# XDM-3_3_SCH.net
KiCad netlist of a schematic drawn in Altium Designer
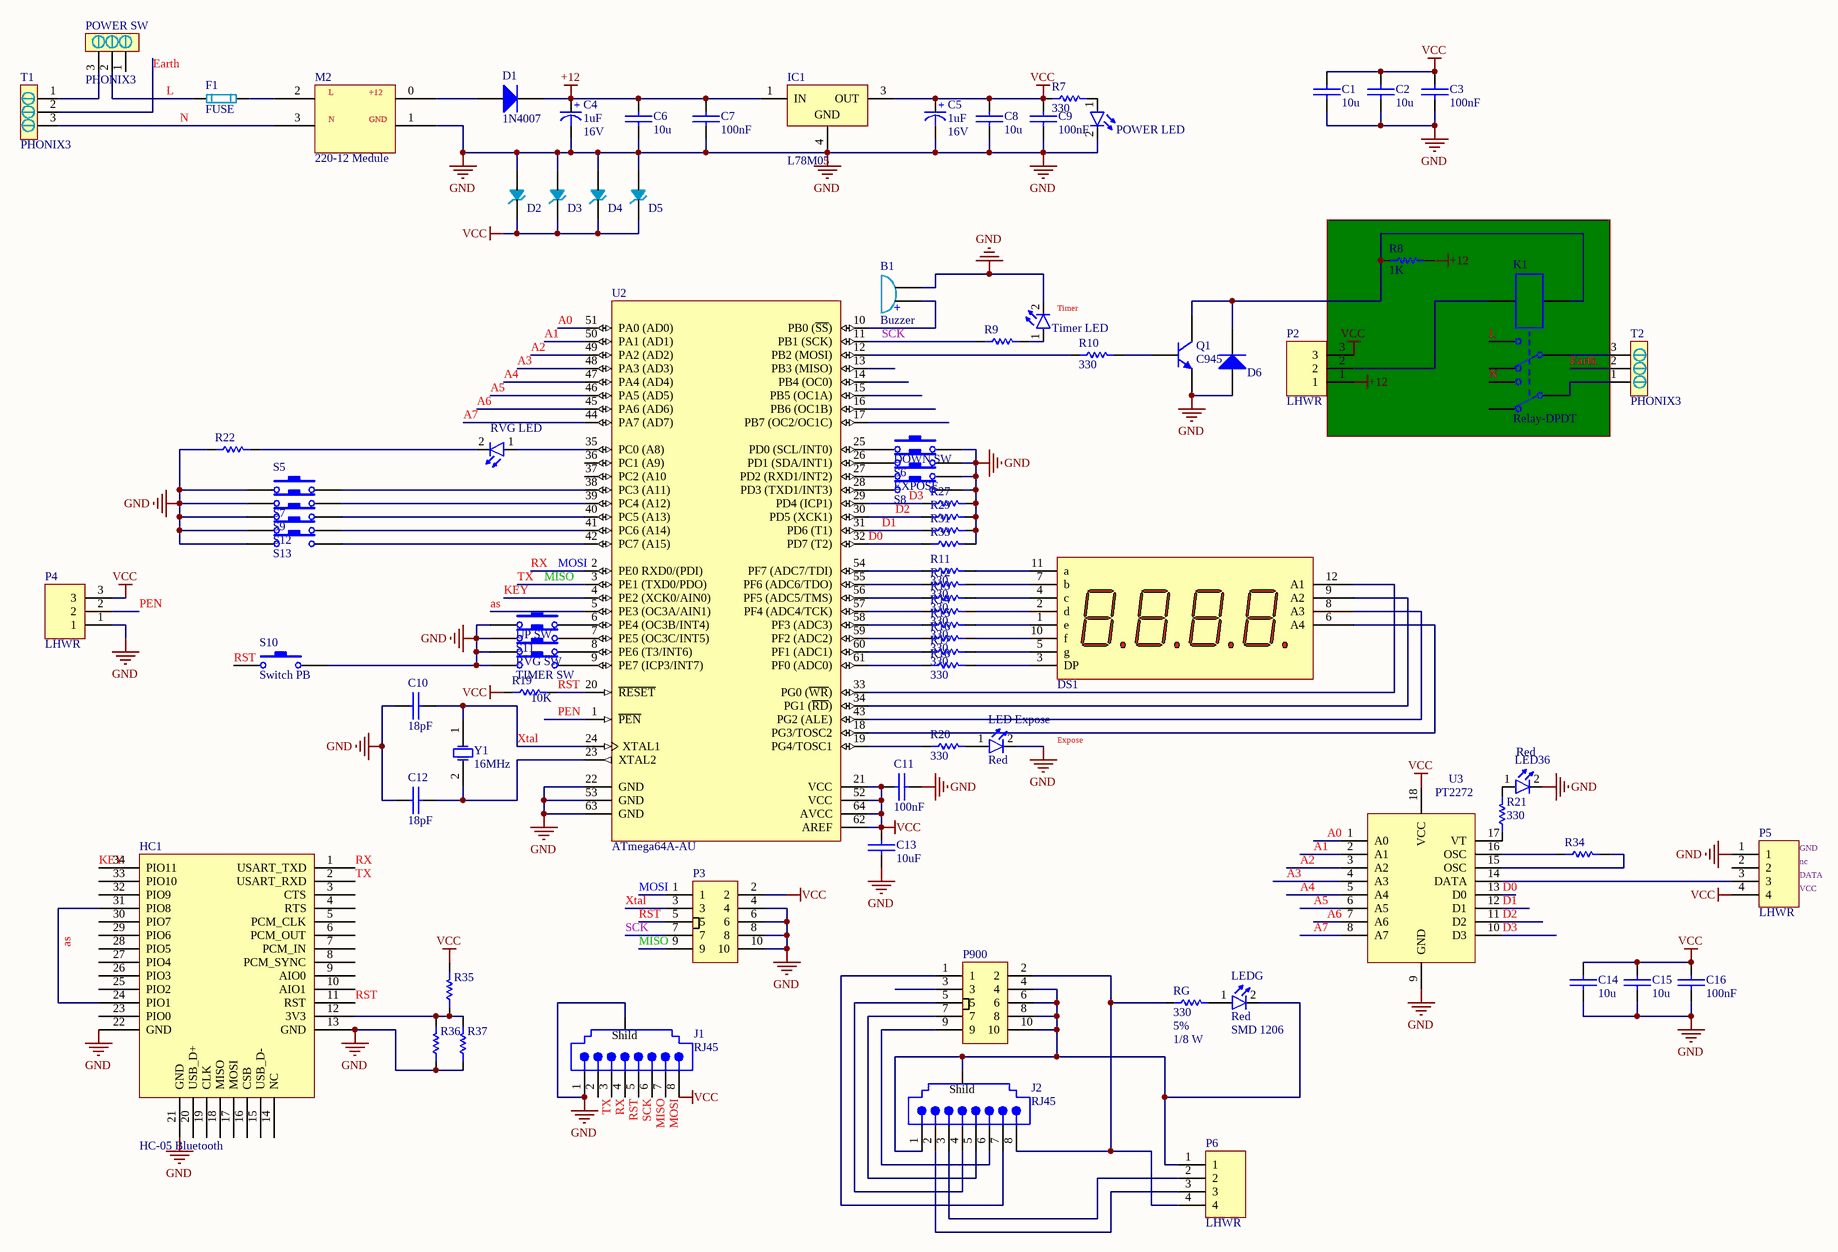
[diagram p0: XDM-3.3_SCH.SchDoc]

(export (version "E")
  (design (tool "Eeschema 10.0.6"))
  (components
    (comp (ref "B1")
      (value "Buzzer")
      (footprint "Buzzer")
      (fields (field (name "DESIGNER") "Hamed Jafarzadeh"))
      (libsource (lib "R2T Team Library") (part "Buzzer"))
    )
    (comp (ref "C1")
      (value "10u")
      (footprint "SMD_CAP_1206")
      (description "Bipolar Capacitor")
      (fields (field (name "VOLTAGE") "100V") (field (name "DESIGNER") "Saeid Jorablo"))
      (libsource (lib "My Library") (part "Cap-Bipolar"))
    )
    (comp (ref "C2")
      (value "10u")
      (footprint "SMD_CAP_1206")
      (description "Bipolar Capacitor")
      (fields (field (name "VOLTAGE") "100V") (field (name "DESIGNER") "Saeid Jorablo"))
      (libsource (lib "My Library") (part "Cap-Bipolar"))
    )
    (comp (ref "C3")
      (value "100nF")
      (footprint "SMD_CAP_1206")
      (description "Bipolar Capacitor")
      (fields (field (name "VOLTAGE") "100V") (field (name "DESIGNER") "Saeid Jorablo"))
      (libsource (lib "My Library") (part "Cap-Bipolar"))
    )
    (comp (ref "C4")
      (value "1uF")
      (footprint "cap 04")
      (description "Polar Capacitor")
      (fields (field (name "VOLTAGE") "16V") (field (name "DESIGNER") "Saeid Jorablo"))
      (libsource (lib "My Library") (part "Cap-Polar"))
    )
    (comp (ref "C5")
      (value "1uF")
      (footprint "cap 04")
      (description "Polar Capacitor")
      (fields (field (name "VOLTAGE") "16V") (field (name "DESIGNER") "Saeid Jorablo"))
      (libsource (lib "My Library") (part "Cap-Polar"))
    )
    (comp (ref "C6")
      (value "10u")
      (footprint "SMD_CAP_1206")
      (description "Bipolar Capacitor")
      (fields (field (name "VOLTAGE") "100V") (field (name "DESIGNER") "Saeid Jorablo"))
      (libsource (lib "My Library") (part "Cap-Bipolar"))
    )
    (comp (ref "C7")
      (value "100nF")
      (footprint "SMD_CAP_1206")
      (description "Bipolar Capacitor")
      (fields (field (name "VOLTAGE") "100V") (field (name "DESIGNER") "Saeid Jorablo"))
      (libsource (lib "My Library") (part "Cap-Bipolar"))
    )
    (comp (ref "C8")
      (value "10u")
      (footprint "SMD_CAP_1206")
      (description "Bipolar Capacitor")
      (fields (field (name "VOLTAGE") "100V") (field (name "DESIGNER") "Saeid Jorablo"))
      (libsource (lib "My Library") (part "Cap-Bipolar"))
    )
    (comp (ref "C9")
      (value "100nF")
      (footprint "SMD_CAP_1206")
      (description "Bipolar Capacitor")
      (fields (field (name "VOLTAGE") "100V") (field (name "DESIGNER") "Saeid Jorablo"))
      (libsource (lib "My Library") (part "Cap-Bipolar"))
    )
    (comp (ref "C10")
      (value "18pF")
      (footprint "SMD_CAP_0805")
      (description "Bipolar Capacitor")
      (fields (field (name "VOLTAGE") "100V") (field (name "DESIGNER") "Saeid Jorablo"))
      (libsource (lib "My Library") (part "Cap-Bipolar"))
    )
    (comp (ref "C11")
      (value "100nF")
      (footprint "SMD_CAP_0805")
      (description "Bipolar Capacitor")
      (fields (field (name "VOLTAGE") "100V") (field (name "DESIGNER") "Saeid Jorablo"))
      (libsource (lib "My Library") (part "Cap-Bipolar"))
    )
    (comp (ref "C12")
      (value "18pF")
      (footprint "SMD_CAP_0805")
      (description "Bipolar Capacitor")
      (fields (field (name "VOLTAGE") "100V") (field (name "DESIGNER") "Saeid Jorablo"))
      (libsource (lib "My Library") (part "Cap-Bipolar"))
    )
    (comp (ref "C13")
      (value "10uF")
      (footprint "SMD_CAP_1206")
      (description "Bipolar Capacitor")
      (fields (field (name "VOLTAGE") "100V") (field (name "DESIGNER") "Saeid Jorablo"))
      (libsource (lib "My Library") (part "Cap-Bipolar"))
    )
    (comp (ref "C14")
      (value "10u")
      (footprint "SMD_CAP_1206")
      (description "Bipolar Capacitor")
      (fields (field (name "VOLTAGE") "100V") (field (name "DESIGNER") "Saeid Jorablo"))
      (libsource (lib "My Library") (part "Cap-Bipolar"))
    )
    (comp (ref "C15")
      (value "10u")
      (footprint "SMD_CAP_1206")
      (description "Bipolar Capacitor")
      (fields (field (name "VOLTAGE") "100V") (field (name "DESIGNER") "Saeid Jorablo"))
      (libsource (lib "My Library") (part "Cap-Bipolar"))
    )
    (comp (ref "C16")
      (value "100nF")
      (footprint "SMD_CAP_1206")
      (description "Bipolar Capacitor")
      (fields (field (name "VOLTAGE") "100V") (field (name "DESIGNER") "Saeid Jorablo"))
      (libsource (lib "My Library") (part "Cap-Bipolar"))
    )
    (comp (ref "D1")
      (value "1N4007")
      (footprint "My_DO-41")
      (description "1 Amp Diode")
      (libsource (lib "MyAltiumLib1") (part "1N4007"))
    )
    (comp (ref "D2")
      (value "Diode Zener SMD")
      (footprint "DIOMELF3615N")
      (fields (field (name "DESIGNER") "Hamed Jafarzadeh"))
      (libsource (lib "R2T Team Library") (part "Diode Zener SMD"))
    )
    (comp (ref "D3")
      (value "Diode Zener SMD")
      (footprint "DIOMELF3615N")
      (fields (field (name "DESIGNER") "Hamed Jafarzadeh"))
      (libsource (lib "R2T Team Library") (part "Diode Zener SMD"))
    )
    (comp (ref "D4")
      (value "Diode Zener SMD")
      (footprint "DIOMELF3615N")
      (fields (field (name "DESIGNER") "Hamed Jafarzadeh"))
      (libsource (lib "R2T Team Library") (part "Diode Zener SMD"))
    )
    (comp (ref "D5")
      (value "Diode Zener SMD")
      (footprint "DIOMELF3615N")
      (fields (field (name "DESIGNER") "Hamed Jafarzadeh"))
      (libsource (lib "R2T Team Library") (part "Diode Zener SMD"))
    )
    (comp (ref "D6")
      (value "1N4007")
      (footprint "My_DO-41")
      (description "1 Amp Diode")
      (libsource (lib "MyAltiumLib1") (part "1N4007"))
    )
    (comp (ref "DOWN SW")
      (value "Switch PB")
      (footprint "Switch - Push to On")
      (description "Push Button Switch")
      (libsource (lib "Electrovolt Lib") (part "Switch PB"))
    )
    (comp (ref "DS1")
      (value "7Segment-4Digit-CA")
      (footprint "7segCA")
      (description "7-Segment Display: CA")
      (fields (field (name "PUBLISHER") "www.picpars.com") (field (name "DESIGNER") "Seyed Mohsen Ghasemain"))
      (libsource (lib "usefully_Library") (part "7Seg-4Digit-CA"))
    )
    (comp (ref "EXPOSE")
      (value "Switch PB")
      (footprint "Switch - Push to On")
      (description "Push Button Switch")
      (libsource (lib "Electrovolt Lib") (part "Switch PB"))
    )
    (comp (ref "F1") (value "FUSE") (footprint "FUSE_1") (libsource (lib "Devices") (part "FUSE")))
    (comp (ref "HC1")
      (value "HC-05 Bluetooth")
      (footprint "HC-05")
      (libsource (lib "R2T Team Library") (part "HC-05 Bluetooth"))
    )
    (comp (ref "IC1")
      (value "L78M05")
      (footprint "TO-252")
      (description "Precision 500mA Regulator")
      (libsource (lib "My Library") (part "L78M05"))
    )
    (comp (ref "J1")
      (value "RJ45")
      (footprint "My_RJ45")
      (description "Right Angle, Standard Profile, RJ45-Keyed, Flange Mount PCB Jack")
      (fields (field (name "PUBLISHER") "Altium Limited"))
      (libsource (lib "MyAltiumLib1") (part "RJ45"))
    )
    (comp (ref "J2")
      (value "RJ45")
      (footprint "My_RJ45")
      (description "Right Angle, Standard Profile, RJ45-Keyed, Flange Mount PCB Jack")
      (fields (field (name "PUBLISHER") "Altium Limited"))
      (libsource (lib "MyAltiumLib1") (part "RJ45"))
    )
    (comp (ref "K1")
      (value "Relay-DPDT")
      (footprint "My_REL_cochick")
      (description "Dual-Pole Dual-Throw Relay")
      (fields (field (name "PUBLISHER") "Altium Limited"))
      (libsource (lib "MyAltiumLib1") (part "Relay-DPDT"))
    )
    (comp (ref "LED Expose")
      (value "Red")
      (footprint "LED-3mm")
      (description "LED")
      (fields (field (name "COLOR") "Red") (field (name "DESIGNER") "Saeid Jorablo"))
      (libsource (lib "My Library") (part "LED"))
    )
    (comp (ref "LED36")
      (value "Red")
      (footprint "LED-3mm")
      (description "LED")
      (fields (field (name "COLOR") "Red") (field (name "DESIGNER") "Saeid Jorablo"))
      (libsource (lib "My Library") (part "LED"))
    )
    (comp (ref "LEDG")
      (value "Red")
      (footprint "LED-3mm")
      (description "LED")
      (fields
        (field (name "COLOR") "Red")
        (field (name "SIZE") "SMD 1206")
        (field (name "DESIGNER") "Saeid Jorablo")
      )
      (libsource (lib "My Library") (part "LED"))
    )
    (comp (ref "M2")
      (value "220-12 Medule")
      (footprint "AC-DC 220-12")
      (libsource (lib "Soga Library") (part "220-12 Medule"))
    )
    (comp (ref "P2")
      (value "LHWR")
      (footprint "Polarized Header 3")
      (fields (field (name "DESIGNER:") "Hamed Jafarzadeh - www.R2T.ir"))
      (libsource (lib "R2T Team Library") (part "3pin LHWR"))
    )
    (comp (ref "P3")
      (value "BoxHeader 2x5")
      (footprint "Box Header 2x5")
      (fields (field (name "DESIGNER") "HamedJafarzadeh - ww.R2T.ir"))
      (libsource (lib "R2T Team Library") (part "BoxHeader 2x5"))
    )
    (comp (ref "P4")
      (value "LHWR")
      (footprint "Polarized Header 3")
      (fields (field (name "DESIGNER:") "Hamed Jafarzadeh - www.R2T.ir"))
      (libsource (lib "R2T Team Library") (part "3pin LHWR"))
    )
    (comp (ref "P5")
      (value "LHWR")
      (footprint "Polarized Header 4")
      (fields (field (name "DESIGNER:") "Hamed Jafarzadeh - www.R2T.ir"))
      (libsource (lib "R2T Team Library") (part "4pin LHWR"))
    )
    (comp (ref "P6")
      (value "LHWR")
      (footprint "Polarized Header 4")
      (fields (field (name "DESIGNER:") "Hamed Jafarzadeh - www.R2T.ir"))
      (libsource (lib "R2T Team Library") (part "4pin LHWR"))
    )
    (comp (ref "P900")
      (value "BoxHeader 2x5")
      (footprint "Box Header 2x5")
      (fields (field (name "DESIGNER") "HamedJafarzadeh - ww.R2T.ir"))
      (libsource (lib "R2T Team Library") (part "BoxHeader 2x5"))
    )
    (comp (ref "POWER LED")
      (value "Red")
      (footprint "LED-3mm")
      (description "LED")
      (fields (field (name "DESIGNER") "Saeid Jorablo"))
      (libsource (lib "My Library") (part "LED"))
    )
    (comp (ref "POWER SW")
      (value "PHONIX3")
      (footprint "PHONIX3")
      (libsource (lib "My_lib_new") (part "PHONIX3"))
    )
    (comp (ref "Q1")
      (value "C945")
      (footprint "C945")
      (description "NPN Transistor")
      (fields (field (name "DESIGNER") "Saeid Jorablo"))
      (libsource (lib "Electrovolt Lib") (part "C945"))
    )
    (comp (ref "R7")
      (value "330")
      (footprint "RES 0805 (2012X06L)")
      (description "Resistor")
      (fields (field (name "TOLERANCE") "5%") (field (name "POWER") "1/8 W"))
      (libsource (lib "My Library") (part "Resistor"))
    )
    (comp (ref "R8")
      (value "1K")
      (footprint "RES 0805 (2012X06L)")
      (description "Resistor")
      (fields (field (name "TOLERANCE") "5%") (field (name "POWER") "1/8 W"))
      (libsource (lib "My Library") (part "Resistor"))
    )
    (comp (ref "R9")
      (value "330")
      (footprint "RES 0805 (2012X06L)")
      (description "Resistor")
      (fields (field (name "TOLERANCE") "5%") (field (name "POWER") "1/8 W"))
      (libsource (lib "My Library") (part "Resistor"))
    )
    (comp (ref "R10")
      (value "330")
      (footprint "RES 0805 (2012X06L)")
      (description "Resistor")
      (fields (field (name "TOLERANCE") "5%") (field (name "POWER") "1/8 W"))
      (libsource (lib "Electrovolt Lib") (part "Resistor"))
    )
    (comp (ref "R11")
      (value "330")
      (footprint "RES 0805 (2012X06L)")
      (description "Resistor")
      (fields (field (name "TOLERANCE") "5%") (field (name "POWER") "1/8 W"))
      (libsource (lib "My Library") (part "Resistor"))
    )
    (comp (ref "R12")
      (value "330")
      (footprint "RES 0805 (2012X06L)")
      (description "Resistor")
      (fields (field (name "TOLERANCE") "5%") (field (name "POWER") "1/8 W"))
      (libsource (lib "My Library") (part "Resistor"))
    )
    (comp (ref "R13")
      (value "330")
      (footprint "RES 0805 (2012X06L)")
      (description "Resistor")
      (fields (field (name "TOLERANCE") "5%") (field (name "POWER") "1/8 W"))
      (libsource (lib "My Library") (part "Resistor"))
    )
    (comp (ref "R14")
      (value "330")
      (footprint "RES 0805 (2012X06L)")
      (description "Resistor")
      (fields (field (name "TOLERANCE") "5%") (field (name "POWER") "1/8 W"))
      (libsource (lib "My Library") (part "Resistor"))
    )
    (comp (ref "R15")
      (value "330")
      (footprint "RES 0805 (2012X06L)")
      (description "Resistor")
      (fields (field (name "TOLERANCE") "5%") (field (name "POWER") "1/8 W"))
      (libsource (lib "My Library") (part "Resistor"))
    )
    (comp (ref "R16")
      (value "330")
      (footprint "RES 0805 (2012X06L)")
      (description "Resistor")
      (fields (field (name "TOLERANCE") "5%") (field (name "POWER") "1/8 W"))
      (libsource (lib "My Library") (part "Resistor"))
    )
    (comp (ref "R17")
      (value "330")
      (footprint "RES 0805 (2012X06L)")
      (description "Resistor")
      (fields (field (name "TOLERANCE") "5%") (field (name "POWER") "1/8 W"))
      (libsource (lib "My Library") (part "Resistor"))
    )
    (comp (ref "R18")
      (value "330")
      (footprint "RES 0805 (2012X06L)")
      (description "Resistor")
      (fields (field (name "TOLERANCE") "5%") (field (name "POWER") "1/8 W"))
      (libsource (lib "My Library") (part "Resistor"))
    )
    (comp (ref "R19")
      (value "10K")
      (footprint "RES 0805 (2012X06L)")
      (description "Resistor")
      (fields (field (name "TOLERANCE") "5%") (field (name "POWER") "1/8 W"))
      (libsource (lib "My Library") (part "Resistor"))
    )
    (comp (ref "R20")
      (value "330")
      (footprint "RES 0805 (2012X06L)")
      (description "Resistor")
      (fields (field (name "TOLERANCE") "5%") (field (name "POWER") "1/8 W"))
      (libsource (lib "My Library") (part "Resistor"))
    )
    (comp (ref "R21")
      (value "330")
      (footprint "RES 0805 (2012X06L)")
      (description "Resistor")
      (fields (field (name "TOLERANCE") "5%") (field (name "POWER") "1/8 W"))
      (libsource (lib "My Library") (part "Resistor"))
    )
    (comp (ref "R22")
      (value "330")
      (footprint "RES 0805 (2012X06L)")
      (description "Resistor")
      (fields (field (name "TOLERANCE") "5%") (field (name "POWER") "1/8 W"))
      (libsource (lib "My Library") (part "Resistor"))
    )
    (comp (ref "R27")
      (value "1K")
      (footprint "RES 0805 (2012X06L)")
      (description "Resistor")
      (fields (field (name "TOLERANCE") "5%") (field (name "POWER") "1/8 W"))
      (libsource (lib "My Library") (part "Resistor"))
    )
    (comp (ref "R29")
      (value "1K")
      (footprint "RES 0805 (2012X06L)")
      (description "Resistor")
      (fields (field (name "TOLERANCE") "5%") (field (name "POWER") "1/8 W"))
      (libsource (lib "My Library") (part "Resistor"))
    )
    (comp (ref "R31")
      (value "1K")
      (footprint "RES 0805 (2012X06L)")
      (description "Resistor")
      (fields (field (name "TOLERANCE") "5%") (field (name "POWER") "1/8 W"))
      (libsource (lib "My Library") (part "Resistor"))
    )
    (comp (ref "R33")
      (value "1K")
      (footprint "RES 0805 (2012X06L)")
      (description "Resistor")
      (fields (field (name "TOLERANCE") "5%") (field (name "POWER") "1/8 W"))
      (libsource (lib "My Library") (part "Resistor"))
    )
    (comp (ref "R34")
      (value "820k")
      (footprint "RES 0805 (2012X06L)")
      (description "Resistor")
      (fields (field (name "TOLERANCE") "5%") (field (name "POWER") "1/8 W"))
      (libsource (lib "My Library") (part "Resistor"))
    )
    (comp (ref "R35")
      (value "51k")
      (footprint "RES 0805 (2012X06L)")
      (description "Resistor")
      (fields (field (name "TOLERANCE") "5%") (field (name "POWER") "1/8 W"))
      (libsource (lib "My Library") (part "Resistor"))
    )
    (comp (ref "R36")
      (value "100k")
      (footprint "RES 0805 (2012X06L)")
      (description "Resistor")
      (fields (field (name "TOLERANCE") "5%") (field (name "POWER") "1/8 W"))
      (libsource (lib "My Library") (part "Resistor"))
    )
    (comp (ref "R37")
      (value "100k")
      (footprint "RES 0805 (2012X06L)")
      (description "Resistor")
      (fields (field (name "TOLERANCE") "5%") (field (name "POWER") "1/8 W"))
      (libsource (lib "My Library") (part "Resistor"))
    )
    (comp (ref "RG")
      (value "330")
      (footprint "RES 0805 (2012X06L)")
      (description "Resistor")
      (fields (field (name "TOLERANCE") "5%") (field (name "POWER") "1/8 W"))
      (libsource (lib "My Library") (part "Resistor"))
    )
    (comp (ref "RVG LED")
      (value "Red")
      (footprint "LED-3mm")
      (description "LED")
      (fields (field (name "DESIGNER") "Saeid Jorablo"))
      (libsource (lib "My Library") (part "LED"))
    )
    (comp (ref "RVG SW")
      (value "Switch PB")
      (footprint "Switch - Push to On")
      (description "Push Button Switch")
      (libsource (lib "Electrovolt Lib") (part "Switch PB"))
    )
    (comp (ref "S5")
      (value "Switch PB")
      (footprint "Switch - Push to On")
      (description "Push Button Switch")
      (libsource (lib "Electrovolt Lib") (part "Switch PB"))
    )
    (comp (ref "S6")
      (value "Switch PB")
      (footprint "Switch - Push to On")
      (description "Push Button Switch")
      (libsource (lib "Electrovolt Lib") (part "Switch PB"))
    )
    (comp (ref "S7")
      (value "Switch PB")
      (footprint "Switch - Push to On")
      (description "Push Button Switch")
      (libsource (lib "Electrovolt Lib") (part "Switch PB"))
    )
    (comp (ref "S8")
      (value "Switch PB")
      (footprint "Switch - Push to On")
      (description "Push Button Switch")
      (libsource (lib "Electrovolt Lib") (part "Switch PB"))
    )
    (comp (ref "S9")
      (value "Switch PB")
      (footprint "Switch - Push to On")
      (description "Push Button Switch")
      (libsource (lib "Electrovolt Lib") (part "Switch PB"))
    )
    (comp (ref "S10")
      (value "Switch PB")
      (footprint "Switch - Push to On")
      (description "Push Button Switch")
      (libsource (lib "Electrovolt Lib") (part "Switch PB"))
    )
    (comp (ref "S11")
      (value "Switch PB")
      (footprint "Switch - Push to On")
      (description "Push Button Switch")
      (libsource (lib "Electrovolt Lib") (part "Switch PB"))
    )
    (comp (ref "S12")
      (value "Switch PB")
      (footprint "Switch - Push to On")
      (description "Push Button Switch")
      (libsource (lib "Electrovolt Lib") (part "Switch PB"))
    )
    (comp (ref "S13")
      (value "Switch PB")
      (footprint "Switch - Push to On")
      (description "Push Button Switch")
      (libsource (lib "Electrovolt Lib") (part "Switch PB"))
    )
    (comp (ref "T1") (value "PHONIX3") (footprint "PHONIX3") (libsource (lib "") (part "PHONIX3_2")))
    (comp (ref "T2") (value "PHONIX3") (footprint "PHONIX3") (libsource (lib "") (part "PHONIX3_1")))
    (comp (ref "Timer LED")
      (value "Red")
      (footprint "LED-3mm")
      (description "LED")
      (fields (field (name "DESIGNER") "Saeid Jorablo"))
      (libsource (lib "My Library") (part "LED"))
    )
    (comp (ref "TIMER SW")
      (value "Switch PB")
      (footprint "Switch - Push to On")
      (description "Push Button Switch")
      (libsource (lib "Electrovolt Lib") (part "Switch PB"))
    )
    (comp (ref "U2")
      (value "ATmega64A-AU")
      (footprint "64A_M")
      (fields (field (name "PUBLISHER") "Altium Limited"))
      (libsource (lib "Atmel Microcontroller 8-Bit megaAVR") (part "ATmega64A-AU"))
    )
    (comp (ref "U3") (value "PT2272") (footprint "DIP18") (libsource (lib "My_lib_new") (part "PT2272")))
    (comp (ref "UP SW")
      (value "Switch PB")
      (footprint "Switch - Push to On")
      (description "Push Button Switch")
      (libsource (lib "Electrovolt Lib") (part "Switch PB"))
    )
    (comp (ref "Y1")
      (value "16MHz")
      (footprint "XTAL Small")
      (description "XTAL Crystal")
      (libsource (lib "My Library") (part "XTAL"))
    )
  )
  (nets
    (net (code "1") (name "+12") (class "Default")
      (node (ref "C4") (pin "1") (pinfunction "+_1") (pintype "passive"))
      (node (ref "C6") (pin "1") (pinfunction "+_1") (pintype "passive"))
      (node (ref "C7") (pin "1") (pinfunction "+_1") (pintype "passive"))
      (node (ref "D1") (pin "K") (pinfunction "K_K") (pintype "passive"))
      (node (ref "IC1") (pin "1") (pinfunction "IN_1") (pintype "power_in"))
      (node (ref "P2") (pin "1") (pinfunction "1_1") (pintype "passive"))
      (node (ref "R8") (pin "2") (pinfunction "2_2") (pintype "passive"))
    )
    (net (code "2") (name "/A0") (class "Default")
      (node (ref "U2") (pin "51") (pinfunction "PA0_(AD0)_51") (pintype "bidirectional"))
      (node (ref "U3") (pin "1") (pinfunction "A0_1") (pintype "passive"))
    )
    (net (code "3") (name "/A1") (class "Default")
      (node (ref "U2") (pin "50") (pinfunction "PA1_(AD1)_50") (pintype "bidirectional"))
      (node (ref "U3") (pin "2") (pinfunction "A1_2") (pintype "passive"))
    )
    (net (code "4") (name "/A2") (class "Default")
      (node (ref "U2") (pin "49") (pinfunction "PA2_(AD2)_49") (pintype "bidirectional"))
      (node (ref "U3") (pin "3") (pinfunction "A2_3") (pintype "passive"))
    )
    (net (code "5") (name "/A3") (class "Default")
      (node (ref "U2") (pin "48") (pinfunction "PA3_(AD3)_48") (pintype "bidirectional"))
      (node (ref "U3") (pin "4") (pinfunction "A3_4") (pintype "passive"))
    )
    (net (code "6") (name "/A4") (class "Default")
      (node (ref "U2") (pin "47") (pinfunction "PA4_(AD4)_47") (pintype "bidirectional"))
      (node (ref "U3") (pin "5") (pinfunction "A4_5") (pintype "passive"))
    )
    (net (code "7") (name "/A5") (class "Default")
      (node (ref "U2") (pin "46") (pinfunction "PA5_(AD5)_46") (pintype "bidirectional"))
      (node (ref "U3") (pin "6") (pinfunction "A5_6") (pintype "passive"))
    )
    (net (code "8") (name "/A6") (class "Default")
      (node (ref "U2") (pin "45") (pinfunction "PA6_(AD6)_45") (pintype "bidirectional"))
      (node (ref "U3") (pin "7") (pinfunction "A6_7") (pintype "passive"))
    )
    (net (code "9") (name "/A7") (class "Default")
      (node (ref "U2") (pin "44") (pinfunction "PA7_(AD7)_44") (pintype "bidirectional"))
      (node (ref "U3") (pin "8") (pinfunction "A7_8") (pintype "passive"))
    )
    (net (code "10") (name "/D0") (class "Default")
      (node (ref "R33") (pin "1") (pinfunction "1_1") (pintype "passive"))
      (node (ref "U2") (pin "32") (pinfunction "PD7_(T2)_32") (pintype "bidirectional"))
      (node (ref "U3") (pin "13") (pinfunction "D0_13") (pintype "passive"))
    )
    (net (code "11") (name "/D1") (class "Default")
      (node (ref "R31") (pin "1") (pinfunction "1_1") (pintype "passive"))
      (node (ref "U2") (pin "31") (pinfunction "PD6_(T1)_31") (pintype "bidirectional"))
      (node (ref "U3") (pin "12") (pinfunction "D1_12") (pintype "passive"))
    )
    (net (code "12") (name "/D2") (class "Default")
      (node (ref "R29") (pin "1") (pinfunction "1_1") (pintype "passive"))
      (node (ref "U2") (pin "30") (pinfunction "PD5_(XCK1)_30") (pintype "bidirectional"))
      (node (ref "U3") (pin "11") (pinfunction "D2_11") (pintype "passive"))
    )
    (net (code "13") (name "/D3") (class "Default")
      (node (ref "R27") (pin "1") (pinfunction "1_1") (pintype "passive"))
      (node (ref "U2") (pin "29") (pinfunction "PD4_(ICP1)_29") (pintype "bidirectional"))
      (node (ref "U3") (pin "10") (pinfunction "D3_10") (pintype "passive"))
    )
    (net (code "14") (name "/Earth") (class "Default")
      (node (ref "T1") (pin "2") (pintype "passive"))
      (node (ref "T2") (pin "2") (pintype "passive"))
    )
    (net (code "15") (name "/KEY") (class "Default")
      (node (ref "HC1") (pin "34") (pinfunction "PIO11_34") (pintype "passive"))
      (node (ref "U2") (pin "4") (pinfunction "PE2_(XCK0/AIN0)_4") (pintype "bidirectional"))
    )
    (net (code "16") (name "/L") (class "Default")
      (node (ref "F1") (pin "1") (pintype "passive"))
      (node (ref "K1") (pin "S1") (pinfunction "S1_S1") (pintype "passive"))
      (node (ref "POWER SW") (pin "2") (pintype "passive"))
    )
    (net (code "17") (name "/MISO") (class "Default")
      (node (ref "HC1") (pin "2") (pinfunction "USART_RXD_2") (pintype "passive"))
      (node (ref "J1") (pin "2") (pinfunction "2_2") (pintype "passive"))
      (node (ref "J1") (pin "6") (pinfunction "6_6") (pintype "passive"))
      (node (ref "P3") (pin "9") (pinfunction "9_9") (pintype "passive"))
      (node (ref "U2") (pin "3") (pinfunction "PE1_(TXD0/PDO)_3") (pintype "bidirectional"))
    )
    (net (code "18") (name "/MOSI") (class "Default")
      (node (ref "HC1") (pin "1") (pinfunction "USART_TXD_1") (pintype "passive"))
      (node (ref "J1") (pin "3") (pinfunction "3_3") (pintype "passive"))
      (node (ref "J1") (pin "7") (pinfunction "7_7") (pintype "passive"))
      (node (ref "P3") (pin "1") (pinfunction "1_1") (pintype "passive"))
      (node (ref "U2") (pin "2") (pinfunction "PE0_RXD0/(PDI)_2") (pintype "bidirectional"))
    )
    (net (code "19") (name "/N") (class "Default")
      (node (ref "K1") (pin "S2") (pinfunction "S2_S2") (pintype "passive"))
      (node (ref "M2") (pin "3") (pinfunction "3_3") (pintype "passive"))
      (node (ref "T1") (pin "3") (pintype "passive"))
    )
    (net (code "20") (name "/PEN") (class "Default")
      (node (ref "P4") (pin "2") (pinfunction "2_2") (pintype "passive"))
      (node (ref "U2") (pin "1") (pinfunction "~{PEN}_1") (pintype "input"))
    )
    (net (code "21") (name "/RST") (class "Default")
      (node (ref "HC1") (pin "11") (pinfunction "RST_11") (pintype "passive"))
      (node (ref "J1") (pin "4") (pinfunction "4_4") (pintype "passive"))
      (node (ref "P3") (pin "5") (pinfunction "5_5") (pintype "passive"))
      (node (ref "R19") (pin "2") (pinfunction "2_2") (pintype "passive"))
      (node (ref "S10") (pin "1") (pinfunction "1_1") (pintype "passive"))
      (node (ref "U2") (pin "20") (pinfunction "~{RESET}_20") (pintype "input"))
    )
    (net (code "22") (name "/SCK") (class "Default")
      (node (ref "J1") (pin "5") (pinfunction "5_5") (pintype "passive"))
      (node (ref "P3") (pin "7") (pinfunction "7_7") (pintype "passive"))
      (node (ref "R9") (pin "1") (pinfunction "1_1") (pintype "passive"))
      (node (ref "U2") (pin "11") (pinfunction "PB1_(SCK)_11") (pintype "bidirectional"))
    )
    (net (code "23") (name "/Xtal") (class "Default")
      (node (ref "C10") (pin "2") (pinfunction "-_2") (pintype "passive"))
      (node (ref "P3") (pin "3") (pinfunction "3_3") (pintype "passive"))
      (node (ref "U2") (pin "24") (pinfunction "XTAL1_24") (pintype "input"))
      (node (ref "Y1") (pin "1") (pinfunction "OSC1_1") (pintype "passive"))
    )
    (net (code "24") (name "/as") (class "Default")
      (node (ref "HC1") (pin "24") (pinfunction "PIO1_24") (pintype "passive"))
      (node (ref "HC1") (pin "31") (pinfunction "PIO8_31") (pintype "passive"))
      (node (ref "U2") (pin "5") (pinfunction "PE3_(OC3A/AIN1)_5") (pintype "bidirectional"))
    )
    (net (code "25") (name "GND") (class "Default")
      (node (ref "B1") (pin "2") (pinfunction "GND_2") (pintype "passive"))
      (node (ref "C1") (pin "2") (pinfunction "-_2") (pintype "passive"))
      (node (ref "C10") (pin "1") (pinfunction "+_1") (pintype "passive"))
      (node (ref "C11") (pin "1") (pinfunction "+_1") (pintype "passive"))
      (node (ref "C12") (pin "1") (pinfunction "+_1") (pintype "passive"))
      (node (ref "C13") (pin "2") (pinfunction "-_2") (pintype "passive"))
      (node (ref "C14") (pin "2") (pinfunction "-_2") (pintype "passive"))
      (node (ref "C15") (pin "2") (pinfunction "-_2") (pintype "passive"))
      (node (ref "C16") (pin "2") (pinfunction "-_2") (pintype "passive"))
      (node (ref "C2") (pin "2") (pinfunction "-_2") (pintype "passive"))
      (node (ref "C3") (pin "2") (pinfunction "-_2") (pintype "passive"))
      (node (ref "C4") (pin "2") (pinfunction "-_2") (pintype "passive"))
      (node (ref "C5") (pin "2") (pinfunction "-_2") (pintype "passive"))
      (node (ref "C6") (pin "2") (pinfunction "-_2") (pintype "passive"))
      (node (ref "C7") (pin "2") (pinfunction "-_2") (pintype "passive"))
      (node (ref "C8") (pin "2") (pinfunction "-_2") (pintype "passive"))
      (node (ref "C9") (pin "2") (pinfunction "-_2") (pintype "passive"))
      (node (ref "D2") (pin "2") (pintype "passive"))
      (node (ref "D3") (pin "2") (pintype "passive"))
      (node (ref "D4") (pin "2") (pintype "passive"))
      (node (ref "D5") (pin "2") (pintype "passive"))
      (node (ref "D6") (pin "A") (pinfunction "A_A") (pintype "passive"))
      (node (ref "DOWN SW") (pin "2") (pinfunction "2_2") (pintype "passive"))
      (node (ref "EXPOSE") (pin "2") (pinfunction "2_2") (pintype "passive"))
      (node (ref "HC1") (pin "13") (pinfunction "GND_13") (pintype "passive"))
      (node (ref "HC1") (pin "21") (pinfunction "GND_21") (pintype "passive"))
      (node (ref "HC1") (pin "22") (pinfunction "GND_22") (pintype "passive"))
      (node (ref "IC1") (pin "4") (pinfunction "GND_4") (pintype "power_in"))
      (node (ref "J1") (pin "1") (pinfunction "1_1") (pintype "passive"))
      (node (ref "J1") (pin "shild") (pinfunction "Shild_shild") (pintype "passive"))
      (node (ref "LED Expose") (pin "2") (pinfunction "K_2") (pintype "passive"))
      (node (ref "LED36") (pin "2") (pinfunction "K_2") (pintype "passive"))
      (node (ref "M2") (pin "1") (pinfunction "1_1") (pintype "passive"))
      (node (ref "P3") (pin "10") (pinfunction "10_10") (pintype "passive"))
      (node (ref "P3") (pin "4") (pinfunction "4_4") (pintype "passive"))
      (node (ref "P3") (pin "6") (pinfunction "6_6") (pintype "passive"))
      (node (ref "P3") (pin "8") (pinfunction "8_8") (pintype "passive"))
      (node (ref "P4") (pin "1") (pinfunction "1_1") (pintype "passive"))
      (node (ref "P5") (pin "1") (pinfunction "1_1") (pintype "passive"))
      (node (ref "POWER LED") (pin "2") (pinfunction "K_2") (pintype "passive"))
      (node (ref "Q1") (pin "1") (pinfunction "E_1") (pintype "passive"))
      (node (ref "R22") (pin "1") (pinfunction "1_1") (pintype "passive"))
      (node (ref "R27") (pin "2") (pinfunction "2_2") (pintype "passive"))
      (node (ref "R29") (pin "2") (pinfunction "2_2") (pintype "passive"))
      (node (ref "R31") (pin "2") (pinfunction "2_2") (pintype "passive"))
      (node (ref "R33") (pin "2") (pinfunction "2_2") (pintype "passive"))
      (node (ref "R36") (pin "1") (pinfunction "1_1") (pintype "passive"))
      (node (ref "R37") (pin "1") (pinfunction "1_1") (pintype "passive"))
      (node (ref "RVG SW") (pin "1") (pinfunction "1_1") (pintype "passive"))
      (node (ref "S10") (pin "2") (pinfunction "2_2") (pintype "passive"))
      (node (ref "S11") (pin "1") (pinfunction "1_1") (pintype "passive"))
      (node (ref "S12") (pin "1") (pinfunction "1_1") (pintype "passive"))
      (node (ref "S13") (pin "1") (pinfunction "1_1") (pintype "passive"))
      (node (ref "S5") (pin "1") (pinfunction "1_1") (pintype "passive"))
      (node (ref "S6") (pin "2") (pinfunction "2_2") (pintype "passive"))
      (node (ref "S7") (pin "1") (pinfunction "1_1") (pintype "passive"))
      (node (ref "S8") (pin "2") (pinfunction "2_2") (pintype "passive"))
      (node (ref "S9") (pin "1") (pinfunction "1_1") (pintype "passive"))
      (node (ref "TIMER SW") (pin "1") (pinfunction "1_1") (pintype "passive"))
      (node (ref "Timer LED") (pin "2") (pinfunction "K_2") (pintype "passive"))
      (node (ref "U2") (pin "22") (pinfunction "GND_22") (pintype "power_in"))
      (node (ref "U2") (pin "53") (pinfunction "GND_53") (pintype "power_in"))
      (node (ref "U2") (pin "63") (pinfunction "GND_63") (pintype "power_in"))
      (node (ref "U3") (pin "9") (pinfunction "GND_9") (pintype "passive"))
      (node (ref "UP SW") (pin "1") (pinfunction "1_1") (pintype "passive"))
    )
    (net (code "26") (name "Net-(B1-VCC)") (class "Default")
      (node (ref "B1") (pin "1") (pinfunction "VCC_1") (pintype "passive"))
      (node (ref "U2") (pin "10") (pinfunction "PB0_(~{SS})_10") (pintype "bidirectional"))
    )
    (net (code "27") (name "Net-(C12--)") (class "Default")
      (node (ref "C12") (pin "2") (pinfunction "-_2") (pintype "passive"))
      (node (ref "U2") (pin "23") (pinfunction "XTAL2_23") (pintype "output"))
      (node (ref "Y1") (pin "2") (pinfunction "OSC2_2") (pintype "passive"))
    )
    (net (code "28") (name "Net-(D1-PadA)") (class "Default")
      (node (ref "D1") (pin "A") (pinfunction "A_A") (pintype "passive"))
      (node (ref "M2") (pin "0") (pinfunction "0_0") (pintype "passive"))
    )
    (net (code "29") (name "Net-(DS1-A1)") (class "Default")
      (node (ref "DS1") (pin "12") (pinfunction "A1_12") (pintype "passive"))
      (node (ref "U2") (pin "33") (pinfunction "PG0_(~{WR})_33") (pintype "bidirectional"))
    )
    (net (code "30") (name "Net-(DS1-A2)") (class "Default")
      (node (ref "DS1") (pin "9") (pinfunction "A2_9") (pintype "passive"))
      (node (ref "U2") (pin "34") (pinfunction "PG1_(~{RD})_34") (pintype "bidirectional"))
    )
    (net (code "31") (name "Net-(DS1-A3)") (class "Default")
      (node (ref "DS1") (pin "8") (pinfunction "A3_8") (pintype "passive"))
      (node (ref "U2") (pin "43") (pinfunction "PG2_(ALE)_43") (pintype "bidirectional"))
    )
    (net (code "32") (name "Net-(DS1-A4)") (class "Default")
      (node (ref "DS1") (pin "6") (pinfunction "A4_6") (pintype "passive"))
      (node (ref "U2") (pin "18") (pinfunction "PG3/TOSC2_18") (pintype "bidirectional"))
    )
    (net (code "33") (name "Net-(DS1-DP)") (class "Default")
      (node (ref "DS1") (pin "3") (pinfunction "DP_3") (pintype "passive"))
      (node (ref "R18") (pin "2") (pinfunction "2_2") (pintype "passive"))
    )
    (net (code "34") (name "Net-(DS1-a)") (class "Default")
      (node (ref "DS1") (pin "11") (pinfunction "a_11") (pintype "passive"))
      (node (ref "R11") (pin "2") (pinfunction "2_2") (pintype "passive"))
    )
    (net (code "35") (name "Net-(DS1-b)") (class "Default")
      (node (ref "DS1") (pin "7") (pinfunction "b_7") (pintype "passive"))
      (node (ref "R12") (pin "2") (pinfunction "2_2") (pintype "passive"))
    )
    (net (code "36") (name "Net-(DS1-c)") (class "Default")
      (node (ref "DS1") (pin "4") (pinfunction "c_4") (pintype "passive"))
      (node (ref "R13") (pin "2") (pinfunction "2_2") (pintype "passive"))
    )
    (net (code "37") (name "Net-(DS1-d)") (class "Default")
      (node (ref "DS1") (pin "2") (pinfunction "d_2") (pintype "passive"))
      (node (ref "R14") (pin "2") (pinfunction "2_2") (pintype "passive"))
    )
    (net (code "38") (name "Net-(DS1-e)") (class "Default")
      (node (ref "DS1") (pin "1") (pinfunction "e_1") (pintype "passive"))
      (node (ref "R15") (pin "2") (pinfunction "2_2") (pintype "passive"))
    )
    (net (code "39") (name "Net-(DS1-f)") (class "Default")
      (node (ref "DS1") (pin "10") (pinfunction "f_10") (pintype "passive"))
      (node (ref "R16") (pin "2") (pinfunction "2_2") (pintype "passive"))
    )
    (net (code "40") (name "Net-(DS1-g)") (class "Default")
      (node (ref "DS1") (pin "5") (pinfunction "g_5") (pintype "passive"))
      (node (ref "R17") (pin "2") (pinfunction "2_2") (pintype "passive"))
    )
    (net (code "41") (name "Net-(F1-Pad2)") (class "Default")
      (node (ref "F1") (pin "2") (pintype "passive"))
      (node (ref "M2") (pin "2") (pinfunction "2_2") (pintype "passive"))
    )
    (net (code "42") (name "Net-(HC1-3V3)") (class "Default")
      (node (ref "HC1") (pin "12") (pinfunction "3V3_12") (pintype "passive"))
      (node (ref "R35") (pin "1") (pinfunction "1_1") (pintype "passive"))
      (node (ref "R36") (pin "2") (pinfunction "2_2") (pintype "passive"))
      (node (ref "R37") (pin "2") (pinfunction "2_2") (pintype "passive"))
    )
    (net (code "43") (name "Net-(J2-Pad2)") (class "Default")
      (node (ref "J2") (pin "2") (pinfunction "2_2") (pintype "passive"))
      (node (ref "P6") (pin "3") (pinfunction "3_3") (pintype "passive"))
    )
    (net (code "44") (name "Net-(J2-Pad3)") (class "Default")
      (node (ref "J2") (pin "3") (pinfunction "3_3") (pintype "passive"))
      (node (ref "P6") (pin "2") (pinfunction "2_2") (pintype "passive"))
    )
    (net (code "45") (name "Net-(J2-Pad4)") (class "Default")
      (node (ref "J2") (pin "4") (pinfunction "4_4") (pintype "passive"))
      (node (ref "P900") (pin "5") (pinfunction "5_5") (pintype "passive"))
    )
    (net (code "46") (name "Net-(J2-Pad5)") (class "Default")
      (node (ref "J2") (pin "5") (pinfunction "5_5") (pintype "passive"))
      (node (ref "P900") (pin "7") (pinfunction "7_7") (pintype "passive"))
    )
    (net (code "47") (name "Net-(J2-Pad6)") (class "Default")
      (node (ref "J2") (pin "6") (pinfunction "6_6") (pintype "passive"))
      (node (ref "P900") (pin "9") (pinfunction "9_9") (pintype "passive"))
    )
    (net (code "48") (name "Net-(J2-Pad7)") (class "Default")
      (node (ref "J2") (pin "7") (pinfunction "7_7") (pintype "passive"))
      (node (ref "P900") (pin "1") (pinfunction "1_1") (pintype "passive"))
    )
    (net (code "49") (name "Net-(J2-Pad8)") (class "Default")
      (node (ref "J2") (pin "8") (pinfunction "8_8") (pintype "passive"))
      (node (ref "P6") (pin "4") (pinfunction "4_4") (pintype "passive"))
      (node (ref "P900") (pin "2") (pinfunction "2_2") (pintype "passive"))
      (node (ref "RG") (pin "1") (pinfunction "1_1") (pintype "passive"))
    )
    (net (code "50") (name "Net-(J2-Shild)") (class "Default")
      (node (ref "J2") (pin "1") (pinfunction "1_1") (pintype "passive"))
      (node (ref "J2") (pin "shild") (pinfunction "Shild_shild") (pintype "passive"))
      (node (ref "LEDG") (pin "2") (pinfunction "K_2") (pintype "passive"))
      (node (ref "P6") (pin "1") (pinfunction "1_1") (pintype "passive"))
      (node (ref "P900") (pin "10") (pinfunction "10_10") (pintype "passive"))
      (node (ref "P900") (pin "4") (pinfunction "4_4") (pintype "passive"))
      (node (ref "P900") (pin "6") (pinfunction "6_6") (pintype "passive"))
      (node (ref "P900") (pin "8") (pinfunction "8_8") (pintype "passive"))
    )
    (net (code "51") (name "Net-(K1-Pad2)") (class "Default")
      (node (ref "K1") (pin "2") (pinfunction "2_2") (pintype "passive"))
      (node (ref "P2") (pin "2") (pinfunction "2_2") (pintype "passive"))
    )
    (net (code "52") (name "Net-(K1-PadP1)") (class "Default")
      (node (ref "K1") (pin "P1") (pinfunction "P1_P1") (pintype "passive"))
      (node (ref "T2") (pin "3") (pintype "passive"))
    )
    (net (code "53") (name "Net-(K1-PadP2)") (class "Default")
      (node (ref "K1") (pin "P2") (pinfunction "P2_P2") (pintype "passive"))
      (node (ref "T2") (pin "1") (pintype "passive"))
    )
    (net (code "54") (name "Net-(LED Expose-A)") (class "Default")
      (node (ref "LED Expose") (pin "1") (pinfunction "A_1") (pintype "passive"))
      (node (ref "R20") (pin "2") (pinfunction "2_2") (pintype "passive"))
    )
    (net (code "55") (name "Net-(LED36-A)") (class "Default")
      (node (ref "LED36") (pin "1") (pinfunction "A_1") (pintype "passive"))
      (node (ref "R21") (pin "2") (pinfunction "2_2") (pintype "passive"))
    )
    (net (code "56") (name "Net-(LEDG-A)") (class "Default")
      (node (ref "LEDG") (pin "1") (pinfunction "A_1") (pintype "passive"))
      (node (ref "RG") (pin "2") (pinfunction "2_2") (pintype "passive"))
    )
    (net (code "57") (name "Net-(POWER LED-A)") (class "Default")
      (node (ref "POWER LED") (pin "1") (pinfunction "A_1") (pintype "passive"))
      (node (ref "R7") (pin "2") (pinfunction "2_2") (pintype "passive"))
    )
    (net (code "58") (name "Net-(POWER SW-Pad3)") (class "Default")
      (node (ref "POWER SW") (pin "3") (pintype "passive"))
      (node (ref "T1") (pin "1") (pintype "passive"))
    )
    (net (code "59") (name "Net-(Q1-B)") (class "Default")
      (node (ref "Q1") (pin "3") (pinfunction "B_3") (pintype "passive"))
      (node (ref "R10") (pin "2") (pinfunction "2_2") (pintype "passive"))
    )
    (net (code "60") (name "Net-(Q1-C)") (class "Default")
      (node (ref "D6") (pin "K") (pinfunction "K_K") (pintype "passive"))
      (node (ref "K1") (pin "1") (pinfunction "1_1") (pintype "passive"))
      (node (ref "Q1") (pin "2") (pinfunction "C_2") (pintype "passive"))
      (node (ref "R8") (pin "1") (pinfunction "1_1") (pintype "passive"))
    )
    (net (code "61") (name "Net-(R34-Pad1)") (class "Default")
      (node (ref "R34") (pin "1") (pinfunction "1_1") (pintype "passive"))
      (node (ref "U3") (pin "16") (pinfunction "OSC_16") (pintype "passive"))
    )
    (net (code "62") (name "Net-(R34-Pad2)") (class "Default")
      (node (ref "R34") (pin "2") (pinfunction "2_2") (pintype "passive"))
      (node (ref "U3") (pin "15") (pinfunction "OSC_15") (pintype "passive"))
    )
    (net (code "63") (name "Net-(RVG LED-A)") (class "Default")
      (node (ref "RVG LED") (pin "1") (pinfunction "A_1") (pintype "passive"))
      (node (ref "U2") (pin "35") (pinfunction "PC0_(A8)_35") (pintype "bidirectional"))
    )
    (net (code "64") (name "Net-(RVG LED-K)") (class "Default")
      (node (ref "R22") (pin "2") (pinfunction "2_2") (pintype "passive"))
      (node (ref "RVG LED") (pin "2") (pinfunction "K_2") (pintype "passive"))
    )
    (net (code "65") (name "Net-(Timer LED-A)") (class "Default")
      (node (ref "R9") (pin "2") (pinfunction "2_2") (pintype "passive"))
      (node (ref "Timer LED") (pin "1") (pinfunction "A_1") (pintype "passive"))
    )
    (net (code "66") (name "Net-(U2-PB2_(MOSI))") (class "Default")
      (node (ref "R10") (pin "1") (pinfunction "1_1") (pintype "passive"))
      (node (ref "U2") (pin "12") (pinfunction "PB2_(MOSI)_12") (pintype "bidirectional"))
    )
    (net (code "67") (name "Net-(U2-PC3_(A11))") (class "Default")
      (node (ref "S5") (pin "2") (pinfunction "2_2") (pintype "passive"))
      (node (ref "U2") (pin "38") (pinfunction "PC3_(A11)_38") (pintype "bidirectional"))
    )
    (net (code "68") (name "Net-(U2-PC4_(A12))") (class "Default")
      (node (ref "S7") (pin "2") (pinfunction "2_2") (pintype "passive"))
      (node (ref "U2") (pin "39") (pinfunction "PC4_(A12)_39") (pintype "bidirectional"))
    )
    (net (code "69") (name "Net-(U2-PC5_(A13))") (class "Default")
      (node (ref "S9") (pin "2") (pinfunction "2_2") (pintype "passive"))
      (node (ref "U2") (pin "40") (pinfunction "PC5_(A13)_40") (pintype "bidirectional"))
    )
    (net (code "70") (name "Net-(U2-PC6_(A14))") (class "Default")
      (node (ref "S12") (pin "2") (pinfunction "2_2") (pintype "passive"))
      (node (ref "U2") (pin "41") (pinfunction "PC6_(A14)_41") (pintype "bidirectional"))
    )
    (net (code "71") (name "Net-(U2-PC7_(A15))") (class "Default")
      (node (ref "S13") (pin "2") (pinfunction "2_2") (pintype "passive"))
      (node (ref "U2") (pin "42") (pinfunction "PC7_(A15)_42") (pintype "bidirectional"))
    )
    (net (code "72") (name "Net-(U2-PD0_(SCL{slash}INT0))") (class "Default")
      (node (ref "DOWN SW") (pin "1") (pinfunction "1_1") (pintype "passive"))
      (node (ref "U2") (pin "25") (pinfunction "PD0_(SCL/INT0)_25") (pintype "bidirectional"))
    )
    (net (code "73") (name "Net-(U2-PD1_(SDA{slash}INT1))") (class "Default")
      (node (ref "S6") (pin "1") (pinfunction "1_1") (pintype "passive"))
      (node (ref "U2") (pin "26") (pinfunction "PD1_(SDA/INT1)_26") (pintype "bidirectional"))
    )
    (net (code "74") (name "Net-(U2-PD2_(RXD1{slash}INT2))") (class "Default")
      (node (ref "EXPOSE") (pin "1") (pinfunction "1_1") (pintype "passive"))
      (node (ref "U2") (pin "27") (pinfunction "PD2_(RXD1/INT2)_27") (pintype "bidirectional"))
    )
    (net (code "75") (name "Net-(U2-PD3_(TXD1{slash}INT3))") (class "Default")
      (node (ref "S8") (pin "1") (pinfunction "1_1") (pintype "passive"))
      (node (ref "U2") (pin "28") (pinfunction "PD3_(TXD1/INT3)_28") (pintype "bidirectional"))
    )
    (net (code "76") (name "Net-(U2-PE4_(OC3B{slash}INT4))") (class "Default")
      (node (ref "U2") (pin "6") (pinfunction "PE4_(OC3B/INT4)_6") (pintype "bidirectional"))
      (node (ref "UP SW") (pin "2") (pinfunction "2_2") (pintype "passive"))
    )
    (net (code "77") (name "Net-(U2-PE5_(OC3C{slash}INT5))") (class "Default")
      (node (ref "S11") (pin "2") (pinfunction "2_2") (pintype "passive"))
      (node (ref "U2") (pin "7") (pinfunction "PE5_(OC3C/INT5)_7") (pintype "bidirectional"))
    )
    (net (code "78") (name "Net-(U2-PE6_(T3{slash}INT6))") (class "Default")
      (node (ref "RVG SW") (pin "2") (pinfunction "2_2") (pintype "passive"))
      (node (ref "U2") (pin "8") (pinfunction "PE6_(T3/INT6)_8") (pintype "bidirectional"))
    )
    (net (code "79") (name "Net-(U2-PE7_(ICP3{slash}INT7))") (class "Default")
      (node (ref "TIMER SW") (pin "2") (pinfunction "2_2") (pintype "passive"))
      (node (ref "U2") (pin "9") (pinfunction "PE7_(ICP3/INT7)_9") (pintype "bidirectional"))
    )
    (net (code "80") (name "Net-(U2-PF0_(ADC0))") (class "Default")
      (node (ref "R18") (pin "1") (pinfunction "1_1") (pintype "passive"))
      (node (ref "U2") (pin "61") (pinfunction "PF0_(ADC0)_61") (pintype "bidirectional"))
    )
    (net (code "81") (name "Net-(U2-PF1_(ADC1))") (class "Default")
      (node (ref "R17") (pin "1") (pinfunction "1_1") (pintype "passive"))
      (node (ref "U2") (pin "60") (pinfunction "PF1_(ADC1)_60") (pintype "bidirectional"))
    )
    (net (code "82") (name "Net-(U2-PF2_(ADC2))") (class "Default")
      (node (ref "R16") (pin "1") (pinfunction "1_1") (pintype "passive"))
      (node (ref "U2") (pin "59") (pinfunction "PF2_(ADC2)_59") (pintype "bidirectional"))
    )
    (net (code "83") (name "Net-(U2-PF3_(ADC3))") (class "Default")
      (node (ref "R15") (pin "1") (pinfunction "1_1") (pintype "passive"))
      (node (ref "U2") (pin "58") (pinfunction "PF3_(ADC3)_58") (pintype "bidirectional"))
    )
    (net (code "84") (name "Net-(U2-PF4_(ADC4{slash}TCK))") (class "Default")
      (node (ref "R14") (pin "1") (pinfunction "1_1") (pintype "passive"))
      (node (ref "U2") (pin "57") (pinfunction "PF4_(ADC4/TCK)_57") (pintype "bidirectional"))
    )
    (net (code "85") (name "Net-(U2-PF5_(ADC5{slash}TMS))") (class "Default")
      (node (ref "R13") (pin "1") (pinfunction "1_1") (pintype "passive"))
      (node (ref "U2") (pin "56") (pinfunction "PF5_(ADC5/TMS)_56") (pintype "bidirectional"))
    )
    (net (code "86") (name "Net-(U2-PF6_(ADC6{slash}TDO))") (class "Default")
      (node (ref "R12") (pin "1") (pinfunction "1_1") (pintype "passive"))
      (node (ref "U2") (pin "55") (pinfunction "PF6_(ADC6/TDO)_55") (pintype "bidirectional"))
    )
    (net (code "87") (name "Net-(U2-PF7_(ADC7{slash}TDI))") (class "Default")
      (node (ref "R11") (pin "1") (pinfunction "1_1") (pintype "passive"))
      (node (ref "U2") (pin "54") (pinfunction "PF7_(ADC7/TDI)_54") (pintype "bidirectional"))
    )
    (net (code "88") (name "Net-(U2-PG4{slash}TOSC1)") (class "Default")
      (node (ref "R20") (pin "1") (pinfunction "1_1") (pintype "passive"))
      (node (ref "U2") (pin "19") (pinfunction "PG4/TOSC1_19") (pintype "bidirectional"))
    )
    (net (code "89") (name "Net-(U3-DATA)") (class "Default")
      (node (ref "P5") (pin "3") (pinfunction "3_3") (pintype "passive"))
      (node (ref "U3") (pin "14") (pinfunction "DATA_14") (pintype "passive"))
    )
    (net (code "90") (name "Net-(U3-VT)") (class "Default")
      (node (ref "R21") (pin "1") (pinfunction "1_1") (pintype "passive"))
      (node (ref "U3") (pin "17") (pinfunction "VT_17") (pintype "passive"))
    )
    (net (code "91") (name "VCC") (class "Default")
      (node (ref "C1") (pin "1") (pinfunction "+_1") (pintype "passive"))
      (node (ref "C11") (pin "2") (pinfunction "-_2") (pintype "passive"))
      (node (ref "C13") (pin "1") (pinfunction "+_1") (pintype "passive"))
      (node (ref "C14") (pin "1") (pinfunction "+_1") (pintype "passive"))
      (node (ref "C15") (pin "1") (pinfunction "+_1") (pintype "passive"))
      (node (ref "C16") (pin "1") (pinfunction "+_1") (pintype "passive"))
      (node (ref "C2") (pin "1") (pinfunction "+_1") (pintype "passive"))
      (node (ref "C3") (pin "1") (pinfunction "+_1") (pintype "passive"))
      (node (ref "C5") (pin "1") (pinfunction "+_1") (pintype "passive"))
      (node (ref "C8") (pin "1") (pinfunction "+_1") (pintype "passive"))
      (node (ref "C9") (pin "1") (pinfunction "+_1") (pintype "passive"))
      (node (ref "D2") (pin "1") (pintype "passive"))
      (node (ref "D3") (pin "1") (pintype "passive"))
      (node (ref "D4") (pin "1") (pintype "passive"))
      (node (ref "D5") (pin "1") (pintype "passive"))
      (node (ref "IC1") (pin "3") (pinfunction "OUT_3") (pintype "power_in"))
      (node (ref "J1") (pin "8") (pinfunction "8_8") (pintype "passive"))
      (node (ref "P2") (pin "3") (pinfunction "3_3") (pintype "passive"))
      (node (ref "P3") (pin "2") (pinfunction "2_2") (pintype "passive"))
      (node (ref "P4") (pin "3") (pinfunction "3_3") (pintype "passive"))
      (node (ref "P5") (pin "4") (pinfunction "4_4") (pintype "passive"))
      (node (ref "R19") (pin "1") (pinfunction "1_1") (pintype "passive"))
      (node (ref "R35") (pin "2") (pinfunction "2_2") (pintype "passive"))
      (node (ref "R7") (pin "1") (pinfunction "1_1") (pintype "passive"))
      (node (ref "U2") (pin "21") (pinfunction "VCC_21") (pintype "power_in"))
      (node (ref "U2") (pin "52") (pinfunction "VCC_52") (pintype "power_in"))
      (node (ref "U2") (pin "62") (pinfunction "AREF_62") (pintype "power_in"))
      (node (ref "U2") (pin "64") (pinfunction "AVCC_64") (pintype "power_in"))
      (node (ref "U3") (pin "18") (pinfunction "VCC_18") (pintype "passive"))
    )
    (net (code "92") (name "unconnected-(HC1-AIO0-Pad9)") (class "Default")
      (node (ref "HC1") (pin "9") (pinfunction "AIO0_9") (pintype "passive"))
    )
    (net (code "93") (name "unconnected-(HC1-AIO1-Pad10)") (class "Default")
      (node (ref "HC1") (pin "10") (pinfunction "AIO1_10") (pintype "passive"))
    )
    (net (code "94") (name "unconnected-(HC1-CLK-Pad19)") (class "Default")
      (node (ref "HC1") (pin "19") (pinfunction "CLK_19") (pintype "passive"))
    )
    (net (code "95") (name "unconnected-(HC1-CSB-Pad16)") (class "Default")
      (node (ref "HC1") (pin "16") (pinfunction "CSB_16") (pintype "passive"))
    )
    (net (code "96") (name "unconnected-(HC1-CTS-Pad3)") (class "Default")
      (node (ref "HC1") (pin "3") (pinfunction "CTS_3") (pintype "passive"))
    )
    (net (code "97") (name "unconnected-(HC1-MISO-Pad18)") (class "Default")
      (node (ref "HC1") (pin "18") (pinfunction "MISO_18") (pintype "passive"))
    )
    (net (code "98") (name "unconnected-(HC1-MOSI-Pad17)") (class "Default")
      (node (ref "HC1") (pin "17") (pinfunction "MOSI_17") (pintype "passive"))
    )
    (net (code "99") (name "unconnected-(HC1-NC-Pad14)") (class "Default")
      (node (ref "HC1") (pin "14") (pinfunction "NC_14") (pintype "passive"))
    )
    (net (code "100") (name "unconnected-(HC1-PCM_CLK-Pad5)") (class "Default")
      (node (ref "HC1") (pin "5") (pinfunction "PCM_CLK_5") (pintype "passive"))
    )
    (net (code "101") (name "unconnected-(HC1-PCM_IN-Pad7)") (class "Default")
      (node (ref "HC1") (pin "7") (pinfunction "PCM_IN_7") (pintype "passive"))
    )
    (net (code "102") (name "unconnected-(HC1-PCM_OUT-Pad6)") (class "Default")
      (node (ref "HC1") (pin "6") (pinfunction "PCM_OUT_6") (pintype "passive"))
    )
    (net (code "103") (name "unconnected-(HC1-PCM_SYNC-Pad8)") (class "Default")
      (node (ref "HC1") (pin "8") (pinfunction "PCM_SYNC_8") (pintype "passive"))
    )
    (net (code "104") (name "unconnected-(HC1-PIO0-Pad23)") (class "Default")
      (node (ref "HC1") (pin "23") (pinfunction "PIO0_23") (pintype "passive"))
    )
    (net (code "105") (name "unconnected-(HC1-PIO2-Pad25)") (class "Default")
      (node (ref "HC1") (pin "25") (pinfunction "PIO2_25") (pintype "passive"))
    )
    (net (code "106") (name "unconnected-(HC1-PIO3-Pad26)") (class "Default")
      (node (ref "HC1") (pin "26") (pinfunction "PIO3_26") (pintype "passive"))
    )
    (net (code "107") (name "unconnected-(HC1-PIO4-Pad27)") (class "Default")
      (node (ref "HC1") (pin "27") (pinfunction "PIO4_27") (pintype "passive"))
    )
    (net (code "108") (name "unconnected-(HC1-PIO5-Pad28)") (class "Default")
      (node (ref "HC1") (pin "28") (pinfunction "PIO5_28") (pintype "passive"))
    )
    (net (code "109") (name "unconnected-(HC1-PIO6-Pad29)") (class "Default")
      (node (ref "HC1") (pin "29") (pinfunction "PIO6_29") (pintype "passive"))
    )
    (net (code "110") (name "unconnected-(HC1-PIO7-Pad30)") (class "Default")
      (node (ref "HC1") (pin "30") (pinfunction "PIO7_30") (pintype "passive"))
    )
    (net (code "111") (name "unconnected-(HC1-PIO9-Pad32)") (class "Default")
      (node (ref "HC1") (pin "32") (pinfunction "PIO9_32") (pintype "passive"))
    )
    (net (code "112") (name "unconnected-(HC1-PIO10-Pad33)") (class "Default")
      (node (ref "HC1") (pin "33") (pinfunction "PIO10_33") (pintype "passive"))
    )
    (net (code "113") (name "unconnected-(HC1-RTS-Pad4)") (class "Default")
      (node (ref "HC1") (pin "4") (pinfunction "RTS_4") (pintype "passive"))
    )
    (net (code "114") (name "unconnected-(HC1-USB_D+-Pad20)") (class "Default")
      (node (ref "HC1") (pin "20") (pinfunction "USB_D+_20") (pintype "passive"))
    )
    (net (code "115") (name "unconnected-(HC1-USB_D--Pad15)") (class "Default")
      (node (ref "HC1") (pin "15") (pinfunction "USB_D-_15") (pintype "passive"))
    )
    (net (code "116") (name "unconnected-(K1-PadO1)") (class "Default")
      (node (ref "K1") (pin "O1") (pinfunction "O1_O1") (pintype "passive"))
    )
    (net (code "117") (name "unconnected-(K1-PadO2)") (class "Default")
      (node (ref "K1") (pin "O2") (pinfunction "O2_O2") (pintype "passive"))
    )
    (net (code "118") (name "unconnected-(P5-Pad2)") (class "Default")
      (node (ref "P5") (pin "2") (pinfunction "2_2") (pintype "passive"))
    )
    (net (code "119") (name "unconnected-(P900-Pad3)") (class "Default")
      (node (ref "P900") (pin "3") (pinfunction "3_3") (pintype "passive"))
    )
    (net (code "120") (name "unconnected-(POWER SW-Pad1)") (class "Default")
      (node (ref "POWER SW") (pin "1") (pintype "passive"))
    )
    (net (code "121") (name "unconnected-(U2-PB3_(MISO)-Pad13)") (class "Default")
      (node (ref "U2") (pin "13") (pinfunction "PB3_(MISO)_13") (pintype "bidirectional"))
    )
    (net (code "122") (name "unconnected-(U2-PB4_(OC0)-Pad14)") (class "Default")
      (node (ref "U2") (pin "14") (pinfunction "PB4_(OC0)_14") (pintype "bidirectional"))
    )
    (net (code "123") (name "unconnected-(U2-PB5_(OC1A)-Pad15)") (class "Default")
      (node (ref "U2") (pin "15") (pinfunction "PB5_(OC1A)_15") (pintype "bidirectional"))
    )
    (net (code "124") (name "unconnected-(U2-PB6_(OC1B)-Pad16)") (class "Default")
      (node (ref "U2") (pin "16") (pinfunction "PB6_(OC1B)_16") (pintype "bidirectional"))
    )
    (net (code "125") (name "unconnected-(U2-PB7_(OC2{slash}OC1C)-Pad17)") (class "Default")
      (node (ref "U2") (pin "17") (pinfunction "PB7_(OC2/OC1C)_17") (pintype "bidirectional"))
    )
    (net (code "126") (name "unconnected-(U2-PC1_(A9)-Pad36)") (class "Default")
      (node (ref "U2") (pin "36") (pinfunction "PC1_(A9)_36") (pintype "bidirectional"))
    )
    (net (code "127") (name "unconnected-(U2-PC2_(A10-Pad37)") (class "Default")
      (node (ref "U2") (pin "37") (pinfunction "PC2_(A10_37") (pintype "bidirectional"))
    )
  )
)
